# deel3_processor.net
KiCad netlist of a schematic drawn in Altium Designer
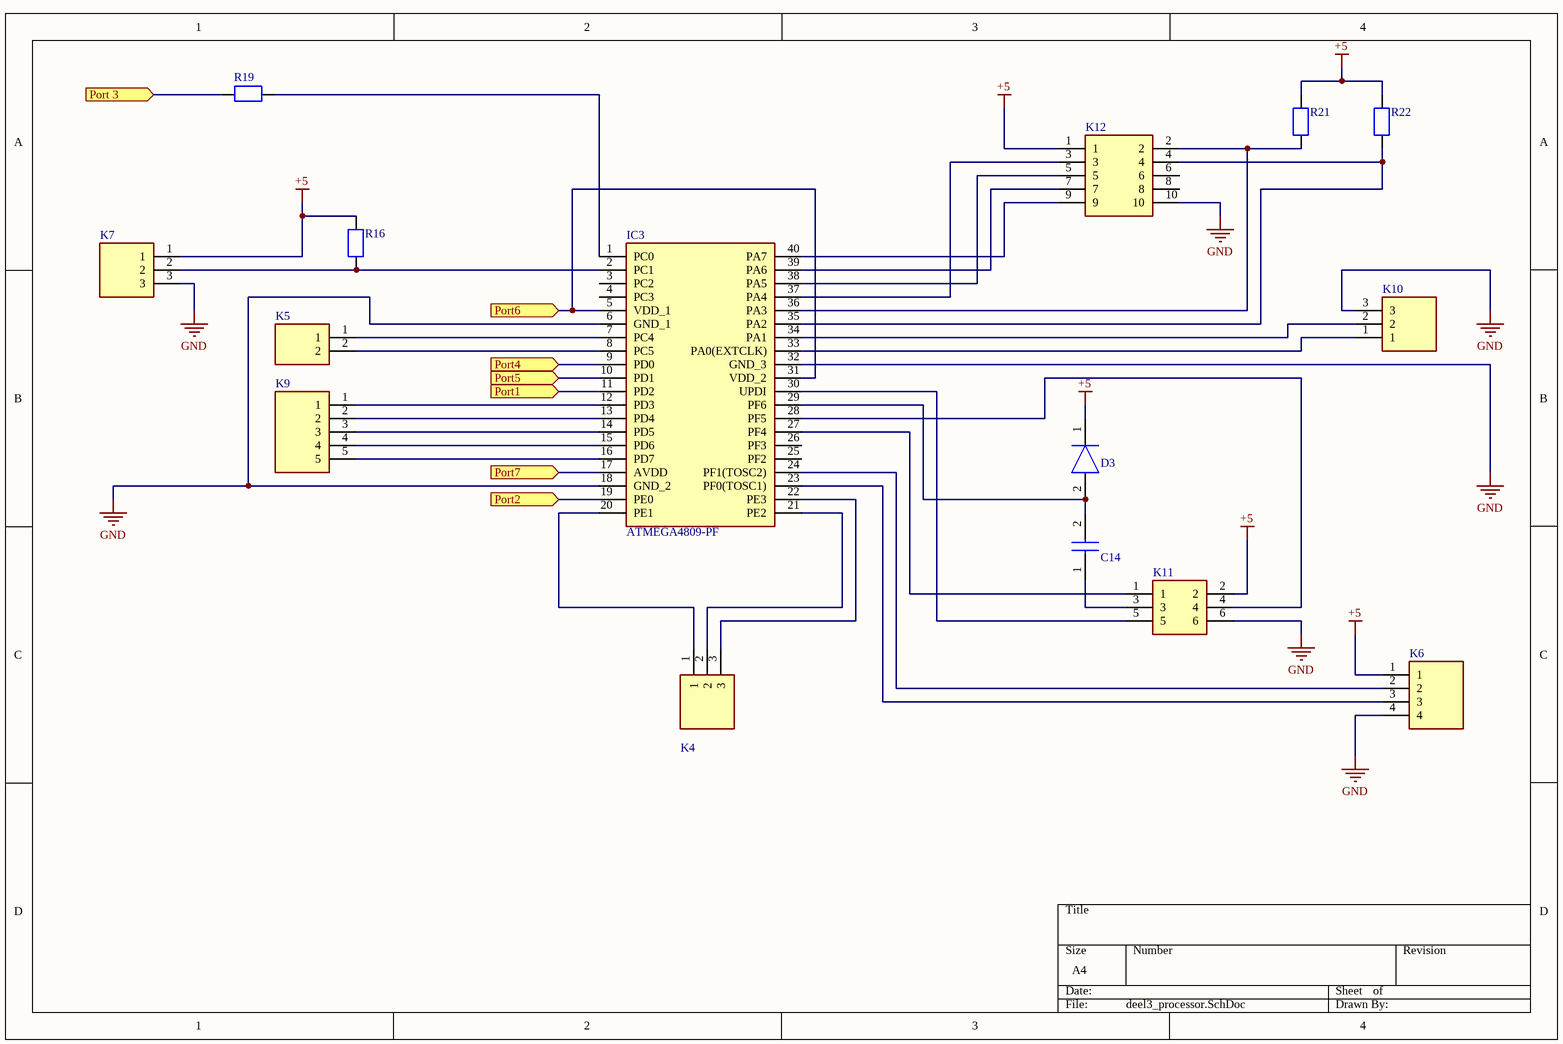
[diagram p0: deel3_processor.SchDoc]

(export (version "E")
  (design (tool "Eeschema 10.0.6"))
  (components
    (comp (ref "C14")
      (value "08055A130JAT2A")
      (footprint "SamacSys:CAPC2012X94N")
      (description "Capacitor")
      (fields (field (name "MOUSER PART NUMBER") "581-08055A130JAT2A"))
      (libsource (lib "SoldeerboutLib") (part "08055A130JAT2A"))
    )
    (comp (ref "D3")
      (value "1N4148")
      (footprint "SamacSys:DIOAD1165W56L425D185")
      (description "Diode")
      (libsource (lib "SoldeerboutLib") (part "1N4148"))
    )
    (comp (ref "IC3")
      (value "ATMEGA4809-PF")
      (footprint "SamacSys:DIP1543W58P254L5175H635Q40N")
      (description "Integrated Circuit")
      (fields (field (name "MOUSER PART NUMBER") "556-ATMEGA4809-PF"))
      (libsource (lib "SoldeerboutLib") (part "ATMEGA4809-PF"))
    )
    (comp (ref "K4")
      (value "10129378-903001BLF")
      (footprint "SamacSys:HDRV3W67P0X254_1X3_762X241X858P")
      (description "Connector")
      (fields (field (name "MOUSER PART NUMBER") "649-1012937890301BLF"))
      (libsource (lib "") (part "10129378-903001BLF_1"))
    )
    (comp (ref "K5")
      (value "10129378-902001BLF")
      (footprint "SamacSys:HDRV2W67P0X254_1X2_508X241X843P")
      (description "Connector")
      (fields (field (name "MOUSER PART NUMBER") "649-1012937890201BLF"))
      (libsource (lib "SoldeerboutLib") (part "10129378-902001BLF"))
    )
    (comp (ref "K6")
      (value "10129378-904001BLF")
      (footprint "SamacSys:HDRV4W67P0X254_1X4_1270X241X858P")
      (description "Connector")
      (fields (field (name "MOUSER PART NUMBER") "649-1012937890401BLF"))
      (libsource (lib "SoldeerboutLib") (part "10129378-904001BLF"))
    )
    (comp (ref "K7")
      (value "10129378-903001BLF")
      (footprint "SamacSys:HDRV3W67P0X254_1X3_762X241X858P")
      (description "Connector")
      (fields (field (name "MOUSER PART NUMBER") "649-1012937890301BLF"))
      (libsource (lib "SoldeerboutLib") (part "10129378-903001BLF"))
    )
    (comp (ref "K9")
      (value "10129378-905001BLF")
      (footprint "SamacSys:HDRV5W67P0X254_1X5_1270X241X858P")
      (description "Connector")
      (fields (field (name "MOUSER PART NUMBER") "649-1012937890501BLF"))
      (libsource (lib "SoldeerboutLib") (part "10129378-905001BLF"))
    )
    (comp (ref "K10")
      (value "10129378-903001BLF")
      (footprint "SamacSys:HDRV3W67P0X254_1X3_762X241X858P")
      (description "Connector")
      (fields (field (name "MOUSER PART NUMBER") "649-1012937890301BLF"))
      (libsource (lib "") (part "10129378-903001BLF_2"))
    )
    (comp (ref "K11")
      (value "10129381-906002BLF")
      (footprint "SamacSys:HDRV6W67P254_2X3_762X483X858P")
      (description "Connector")
      (fields (field (name "MOUSER PART NUMBER") "649-1012938190602BLF"))
      (libsource (lib "SoldeerboutLib") (part "10129381-906002BLF"))
    )
    (comp (ref "K12")
      (value "N2510-6002RB")
      (footprint "SamacSys:SHDR10W64P254_2X5_2002X859X991P")
      (description "Connector")
      (fields (field (name "MOUSER PART NUMBER") "517-N2510-6002RB"))
      (libsource (lib "*") (part "N2510-6002RB"))
    )
    (comp (ref "R16")
      (value "CRCW08050000Z0EA")
      (footprint "RESC2013X50X30LL20T20")
      (description "4k7")
      (fields (field (name "MANUFACTURER") "Vishay Dale"))
      (libsource (lib "SoldeerboutLib") (part "resistor"))
    )
    (comp (ref "R19")
      (value "CRCW08050000Z0EA")
      (footprint "RESC2013X50X30LL20T20")
      (fields (field (name "MANUFACTURER") "Vishay Dale"))
      (libsource (lib "SoldeerboutLib") (part "resistor"))
    )
    (comp (ref "R21")
      (value "CRCW08050000Z0EA")
      (footprint "RESC2013X50X30LL20T20")
      (fields (field (name "MANUFACTURER") "Vishay Dale"))
      (libsource (lib "SoldeerboutLib") (part "resistor"))
    )
    (comp (ref "R22")
      (value "CRCW08050000Z0EA")
      (footprint "RESC2013X50X30LL20T20")
      (fields (field (name "MANUFACTURER") "Vishay Dale"))
      (libsource (lib "SoldeerboutLib") (part "resistor"))
    )
  )
  (nets
    (net (code "1") (name "+5") (class "Default")
      (node (ref "D3") (pin "1") (pinfunction "K_1") (pintype "passive"))
      (node (ref "K11") (pin "2") (pinfunction "2_2") (pintype "passive"))
      (node (ref "K12") (pin "1") (pinfunction "1_1") (pintype "passive"))
      (node (ref "K6") (pin "1") (pinfunction "1_1") (pintype "passive"))
      (node (ref "K7") (pin "1") (pinfunction "1_1") (pintype "passive"))
      (node (ref "R16") (pin "2") (pinfunction "2_2") (pintype "passive"))
      (node (ref "R21") (pin "2") (pinfunction "2_2") (pintype "passive"))
      (node (ref "R22") (pin "2") (pinfunction "2_2") (pintype "passive"))
    )
    (net (code "2") (name "/Port 3") (class "Default")
      (node (ref "R19") (pin "1") (pinfunction "1_1") (pintype "passive"))
    )
    (net (code "3") (name "/Port1") (class "Default")
      (node (ref "IC3") (pin "11") (pinfunction "PD2_11") (pintype "passive"))
    )
    (net (code "4") (name "/Port2") (class "Default")
      (node (ref "IC3") (pin "19") (pinfunction "PE0_19") (pintype "passive"))
    )
    (net (code "5") (name "/Port4") (class "Default")
      (node (ref "IC3") (pin "9") (pinfunction "PD0_9") (pintype "passive"))
    )
    (net (code "6") (name "/Port5") (class "Default")
      (node (ref "IC3") (pin "10") (pinfunction "PD1_10") (pintype "passive"))
    )
    (net (code "7") (name "/Port6") (class "Default")
      (node (ref "IC3") (pin "31") (pinfunction "VDD_2_31") (pintype "passive"))
      (node (ref "IC3") (pin "5") (pinfunction "VDD_1_5") (pintype "passive"))
    )
    (net (code "8") (name "/Port7") (class "Default")
      (node (ref "IC3") (pin "17") (pinfunction "AVDD_17") (pintype "passive"))
    )
    (net (code "9") (name "GND") (class "Default")
      (node (ref "IC3") (pin "18") (pinfunction "GND_2_18") (pintype "passive"))
      (node (ref "IC3") (pin "32") (pinfunction "GND_3_32") (pintype "passive"))
      (node (ref "IC3") (pin "6") (pinfunction "GND_1_6") (pintype "passive"))
      (node (ref "K10") (pin "3") (pinfunction "3_3") (pintype "passive"))
      (node (ref "K11") (pin "6") (pinfunction "6_6") (pintype "passive"))
      (node (ref "K12") (pin "10") (pinfunction "10_10") (pintype "passive"))
      (node (ref "K6") (pin "4") (pinfunction "4_4") (pintype "passive"))
      (node (ref "K7") (pin "3") (pinfunction "3_3") (pintype "passive"))
    )
    (net (code "10") (name "Net-(C14-Pad1)") (class "Default")
      (node (ref "C14") (pin "1") (pinfunction "1_1") (pintype "passive"))
      (node (ref "K11") (pin "3") (pinfunction "3_3") (pintype "passive"))
    )
    (net (code "11") (name "Net-(D3-A)") (class "Default")
      (node (ref "C14") (pin "2") (pinfunction "2_2") (pintype "passive"))
      (node (ref "D3") (pin "2") (pinfunction "A_2") (pintype "passive"))
      (node (ref "IC3") (pin "29") (pinfunction "PF6_29") (pintype "passive"))
    )
    (net (code "12") (name "Net-(IC3-PA0(EXTCLK))") (class "Default")
      (node (ref "IC3") (pin "33") (pinfunction "PA0(EXTCLK)_33") (pintype "passive"))
      (node (ref "K10") (pin "1") (pinfunction "1_1") (pintype "passive"))
    )
    (net (code "13") (name "Net-(IC3-PA1)") (class "Default")
      (node (ref "IC3") (pin "34") (pinfunction "PA1_34") (pintype "passive"))
      (node (ref "K10") (pin "2") (pinfunction "2_2") (pintype "passive"))
    )
    (net (code "14") (name "Net-(IC3-PA2)") (class "Default")
      (node (ref "IC3") (pin "35") (pinfunction "PA2_35") (pintype "passive"))
      (node (ref "K12") (pin "4") (pinfunction "4_4") (pintype "passive"))
      (node (ref "R22") (pin "1") (pinfunction "1_1") (pintype "passive"))
    )
    (net (code "15") (name "Net-(IC3-PA3)") (class "Default")
      (node (ref "IC3") (pin "36") (pinfunction "PA3_36") (pintype "passive"))
      (node (ref "K12") (pin "2") (pinfunction "2_2") (pintype "passive"))
      (node (ref "R21") (pin "1") (pinfunction "1_1") (pintype "passive"))
    )
    (net (code "16") (name "Net-(IC3-PA4)") (class "Default")
      (node (ref "IC3") (pin "37") (pinfunction "PA4_37") (pintype "passive"))
      (node (ref "K12") (pin "3") (pinfunction "3_3") (pintype "passive"))
    )
    (net (code "17") (name "Net-(IC3-PA5)") (class "Default")
      (node (ref "IC3") (pin "38") (pinfunction "PA5_38") (pintype "passive"))
      (node (ref "K12") (pin "5") (pinfunction "5_5") (pintype "passive"))
    )
    (net (code "18") (name "Net-(IC3-PA6)") (class "Default")
      (node (ref "IC3") (pin "39") (pinfunction "PA6_39") (pintype "passive"))
      (node (ref "K12") (pin "7") (pinfunction "7_7") (pintype "passive"))
    )
    (net (code "19") (name "Net-(IC3-PA7)") (class "Default")
      (node (ref "IC3") (pin "40") (pinfunction "PA7_40") (pintype "passive"))
      (node (ref "K12") (pin "9") (pinfunction "9_9") (pintype "passive"))
    )
    (net (code "20") (name "Net-(IC3-PC0)") (class "Default")
      (node (ref "IC3") (pin "1") (pinfunction "PC0_1") (pintype "passive"))
      (node (ref "R19") (pin "2") (pinfunction "2_2") (pintype "passive"))
    )
    (net (code "21") (name "Net-(IC3-PC1)") (class "Default")
      (node (ref "IC3") (pin "2") (pinfunction "PC1_2") (pintype "passive"))
      (node (ref "K7") (pin "2") (pinfunction "2_2") (pintype "passive"))
      (node (ref "R16") (pin "1") (pinfunction "1_1") (pintype "passive"))
    )
    (net (code "22") (name "Net-(IC3-PC4)") (class "Default")
      (node (ref "IC3") (pin "7") (pinfunction "PC4_7") (pintype "passive"))
      (node (ref "K5") (pin "1") (pinfunction "1_1") (pintype "passive"))
    )
    (net (code "23") (name "Net-(IC3-PC5)") (class "Default")
      (node (ref "IC3") (pin "8") (pinfunction "PC5_8") (pintype "passive"))
      (node (ref "K5") (pin "2") (pinfunction "2_2") (pintype "passive"))
    )
    (net (code "24") (name "Net-(IC3-PD3)") (class "Default")
      (node (ref "IC3") (pin "12") (pinfunction "PD3_12") (pintype "passive"))
      (node (ref "K9") (pin "1") (pinfunction "1_1") (pintype "passive"))
    )
    (net (code "25") (name "Net-(IC3-PD4)") (class "Default")
      (node (ref "IC3") (pin "13") (pinfunction "PD4_13") (pintype "passive"))
      (node (ref "K9") (pin "2") (pinfunction "2_2") (pintype "passive"))
    )
    (net (code "26") (name "Net-(IC3-PD5)") (class "Default")
      (node (ref "IC3") (pin "14") (pinfunction "PD5_14") (pintype "passive"))
      (node (ref "K9") (pin "3") (pinfunction "3_3") (pintype "passive"))
    )
    (net (code "27") (name "Net-(IC3-PD6)") (class "Default")
      (node (ref "IC3") (pin "15") (pinfunction "PD6_15") (pintype "passive"))
      (node (ref "K9") (pin "4") (pinfunction "4_4") (pintype "passive"))
    )
    (net (code "28") (name "Net-(IC3-PD7)") (class "Default")
      (node (ref "IC3") (pin "16") (pinfunction "PD7_16") (pintype "passive"))
      (node (ref "K9") (pin "5") (pinfunction "5_5") (pintype "passive"))
    )
    (net (code "29") (name "Net-(IC3-PE1)") (class "Default")
      (node (ref "IC3") (pin "20") (pinfunction "PE1_20") (pintype "passive"))
      (node (ref "K4") (pin "1") (pinfunction "1_1") (pintype "passive"))
    )
    (net (code "30") (name "Net-(IC3-PE2)") (class "Default")
      (node (ref "IC3") (pin "21") (pinfunction "PE2_21") (pintype "passive"))
      (node (ref "K4") (pin "2") (pinfunction "2_2") (pintype "passive"))
    )
    (net (code "31") (name "Net-(IC3-PE3)") (class "Default")
      (node (ref "IC3") (pin "22") (pinfunction "PE3_22") (pintype "passive"))
      (node (ref "K4") (pin "3") (pinfunction "3_3") (pintype "passive"))
    )
    (net (code "32") (name "Net-(IC3-PF0(TOSC1))") (class "Default")
      (node (ref "IC3") (pin "23") (pinfunction "PF0(TOSC1)_23") (pintype "passive"))
      (node (ref "K6") (pin "3") (pinfunction "3_3") (pintype "passive"))
    )
    (net (code "33") (name "Net-(IC3-PF1(TOSC2))") (class "Default")
      (node (ref "IC3") (pin "24") (pinfunction "PF1(TOSC2)_24") (pintype "passive"))
      (node (ref "K6") (pin "2") (pinfunction "2_2") (pintype "passive"))
    )
    (net (code "34") (name "Net-(IC3-PF4)") (class "Default")
      (node (ref "IC3") (pin "27") (pinfunction "PF4_27") (pintype "passive"))
      (node (ref "K11") (pin "1") (pinfunction "1_1") (pintype "passive"))
    )
    (net (code "35") (name "Net-(IC3-PF5)") (class "Default")
      (node (ref "IC3") (pin "28") (pinfunction "PF5_28") (pintype "passive"))
      (node (ref "K11") (pin "4") (pinfunction "4_4") (pintype "passive"))
    )
    (net (code "36") (name "Net-(IC3-UPDI)") (class "Default")
      (node (ref "IC3") (pin "30") (pinfunction "UPDI_30") (pintype "passive"))
      (node (ref "K11") (pin "5") (pinfunction "5_5") (pintype "passive"))
    )
    (net (code "37") (name "unconnected-(IC3-PC2-Pad3)") (class "Default")
      (node (ref "IC3") (pin "3") (pinfunction "PC2_3") (pintype "passive"))
    )
    (net (code "38") (name "unconnected-(IC3-PC3-Pad4)") (class "Default")
      (node (ref "IC3") (pin "4") (pinfunction "PC3_4") (pintype "passive"))
    )
    (net (code "39") (name "unconnected-(IC3-PF2-Pad25)") (class "Default")
      (node (ref "IC3") (pin "25") (pinfunction "PF2_25") (pintype "passive"))
    )
    (net (code "40") (name "unconnected-(IC3-PF3-Pad26)") (class "Default")
      (node (ref "IC3") (pin "26") (pinfunction "PF3_26") (pintype "passive"))
    )
    (net (code "41") (name "unconnected-(K12-Pad6)") (class "Default")
      (node (ref "K12") (pin "6") (pinfunction "6_6") (pintype "passive"))
    )
    (net (code "42") (name "unconnected-(K12-Pad8)") (class "Default")
      (node (ref "K12") (pin "8") (pinfunction "8_8") (pintype "passive"))
    )
  )
)
